# Sheet3.net
KiCad netlist of a schematic drawn in Altium Designer
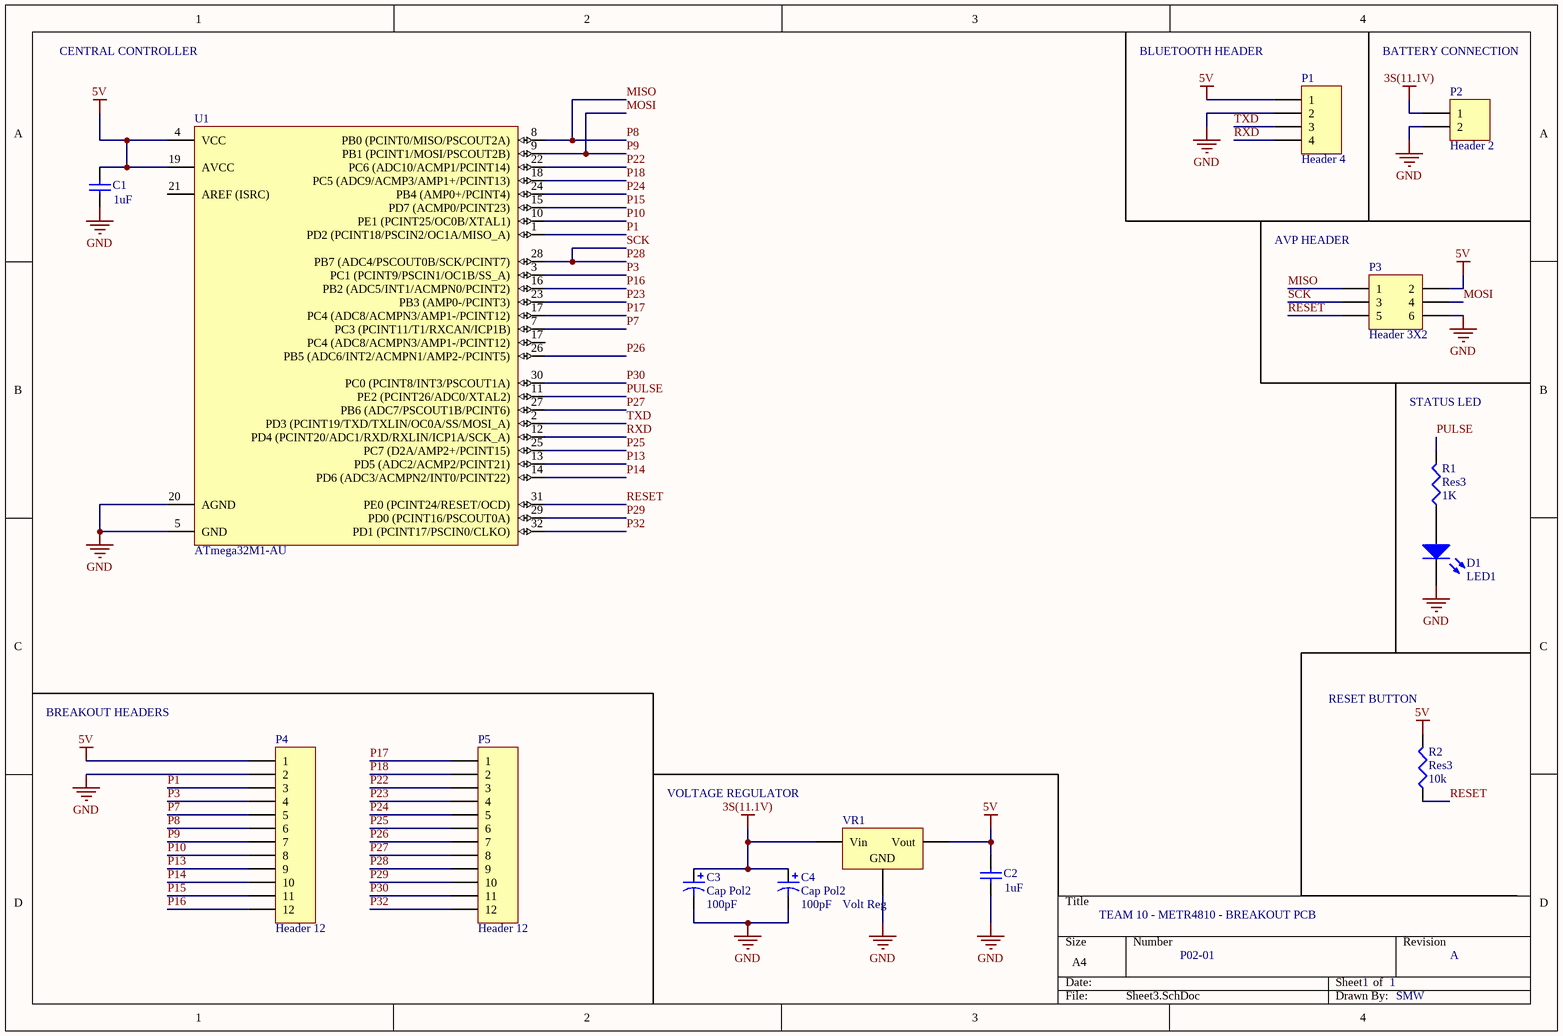
[diagram p0: Sheet3.SchDoc]

(export (version "E")
  (design (tool "Eeschema 10.0.6"))
  (components
    (comp (ref "C1")
      (value "1uF")
      (footprint "1608[0603]")
      (description "Capacitor")
      (fields (field (name "Comment") "Cap") (field (name "PUBLISHER") "Altium Limited"))
      (libsource (lib "Miscellaneous Devices") (part "Cap"))
    )
    (comp (ref "C2")
      (value "1uF")
      (footprint "1608[0603]")
      (description "Capacitor")
      (fields (field (name "Comment") "Cap") (field (name "PUBLISHER") "Altium Limited"))
      (libsource (lib "Miscellaneous Devices") (part "Cap"))
    )
    (comp (ref "C3")
      (value "Cap Pol2")
      (footprint "CAPAE9983X105M")
      (description "Polarized Capacitor (Axial)")
      (fields (field (name "ALTIUM_VALUE") "100pF") (field (name "PUBLISHER") "Altium Limited"))
      (libsource (lib "Miscellaneous Devices") (part "Cap Pol2"))
    )
    (comp (ref "C4")
      (value "Cap Pol2")
      (footprint "CAPAE9983X105M")
      (description "Polarized Capacitor (Axial)")
      (fields (field (name "ALTIUM_VALUE") "100pF") (field (name "PUBLISHER") "Altium Limited"))
      (libsource (lib "Miscellaneous Devices") (part "Cap Pol2"))
    )
    (comp (ref "D1")
      (value "LED1")
      (footprint "L0603")
      (description "Typical RED GaAs LED")
      (fields (field (name "PUBLISHER") "Altium Limited"))
      (libsource (lib "Miscellaneous Devices") (part "LED1"))
    )
    (comp (ref "P1")
      (value "Header 4")
      (footprint "HDR1X4")
      (description "Header, 4-Pin")
      (fields (field (name "PUBLISHER") "Altium Limited"))
      (libsource (lib "Miscellaneous Connectors") (part "Header 4"))
    )
    (comp (ref "P2")
      (value "Header 2")
      (footprint "HDR1X2")
      (description "Header, 2-Pin")
      (fields (field (name "PUBLISHER") "Altium Limited"))
      (libsource (lib "Miscellaneous Connectors") (part "Header 2"))
    )
    (comp (ref "P3")
      (value "Header 3X2")
      (footprint "HDR2X3")
      (description "Header, 3-Pin, Dual row")
      (fields (field (name "PUBLISHER") "Altium Limited"))
      (libsource (lib "Miscellaneous Connectors") (part "Header 3X2"))
    )
    (comp (ref "P4")
      (value "Header 12")
      (footprint "HDR1X12")
      (description "Header, 12-Pin")
      (fields (field (name "PUBLISHER") "Altium Limited"))
      (libsource (lib "Miscellaneous Connectors") (part "Header 12"))
    )
    (comp (ref "P5")
      (value "Header 12")
      (footprint "HDR1X12")
      (description "Header, 12-Pin")
      (fields (field (name "PUBLISHER") "Altium Limited"))
      (libsource (lib "Miscellaneous Connectors") (part "Header 12"))
    )
    (comp (ref "R1")
      (value "Res3")
      (footprint "J1-0603")
      (description "Resistor")
      (fields (field (name "ALTIUM_VALUE") "1K") (field (name "PUBLISHER") "Altium Limited"))
      (libsource (lib "Miscellaneous Devices") (part "Res3"))
    )
    (comp (ref "R2")
      (value "Res3")
      (footprint "J1-0603")
      (description "Resistor")
      (fields (field (name "ALTIUM_VALUE") "10k") (field (name "PUBLISHER") "Altium Limited"))
      (libsource (lib "Miscellaneous Devices") (part "Res3"))
    )
    (comp (ref "U1")
      (value "ATmega32M1-AU")
      (footprint "32A_L")
      (libsource (lib "Atmel Microcontroller AVR Automotive") (part "ATmega32M1-AU"))
    )
    (comp (ref "VR1")
      (value "Volt Reg")
      (footprint "D2PAK_N")
      (description "Voltage Regulator")
      (fields (field (name "PUBLISHER") "Altium Limited"))
      (libsource (lib "Miscellaneous Devices") (part "Volt Reg"))
    )
  )
  (nets
    (net (code "1") (name "/MISO") (class "Default")
      (node (ref "P3") (pin "1") (pinfunction "1_1") (pintype "passive"))
      (node (ref "P4") (pin "6") (pinfunction "6_6") (pintype "passive"))
      (node (ref "U1") (pin "8") (pinfunction "PB0_(PCINT0/MISO/PSCOUT2A)_8") (pintype "bidirectional"))
    )
    (net (code "2") (name "/MOSI") (class "Default")
      (node (ref "P3") (pin "4") (pinfunction "4_4") (pintype "passive"))
      (node (ref "P4") (pin "7") (pinfunction "7_7") (pintype "passive"))
      (node (ref "U1") (pin "9") (pinfunction "PB1_(PCINT1/MOSI/PSCOUT2B)_9") (pintype "bidirectional"))
    )
    (net (code "3") (name "/P1") (class "Default")
      (node (ref "P4") (pin "3") (pinfunction "3_3") (pintype "passive"))
      (node (ref "U1") (pin "1") (pinfunction "PD2_(PCINT18/PSCIN2/OC1A/MISO_A)_1") (pintype "bidirectional"))
    )
    (net (code "4") (name "/P3") (class "Default")
      (node (ref "P4") (pin "4") (pinfunction "4_4") (pintype "passive"))
      (node (ref "U1") (pin "3") (pinfunction "PC1_(PCINT9/PSCIN1/OC1B/SS_A)_3") (pintype "bidirectional"))
    )
    (net (code "5") (name "/P7") (class "Default")
      (node (ref "P4") (pin "5") (pinfunction "5_5") (pintype "passive"))
      (node (ref "U1") (pin "7") (pinfunction "PC3_(PCINT11/T1/RXCAN/ICP1B)_7") (pintype "bidirectional"))
    )
    (net (code "6") (name "/P10") (class "Default")
      (node (ref "P4") (pin "8") (pinfunction "8_8") (pintype "passive"))
      (node (ref "U1") (pin "10") (pinfunction "PE1_(PCINT25/OC0B/XTAL1)_10") (pintype "bidirectional"))
    )
    (net (code "7") (name "/P13") (class "Default")
      (node (ref "P4") (pin "9") (pinfunction "9_9") (pintype "passive"))
      (node (ref "U1") (pin "13") (pinfunction "PD5_(ADC2/ACMP2/PCINT21)_13") (pintype "bidirectional"))
    )
    (net (code "8") (name "/P14") (class "Default")
      (node (ref "P4") (pin "10") (pinfunction "10_10") (pintype "passive"))
      (node (ref "U1") (pin "14") (pinfunction "PD6_(ADC3/ACMPN2/INT0/PCINT22)_14") (pintype "bidirectional"))
    )
    (net (code "9") (name "/P15") (class "Default")
      (node (ref "P4") (pin "11") (pinfunction "11_11") (pintype "passive"))
      (node (ref "U1") (pin "15") (pinfunction "PD7_(ACMP0/PCINT23)_15") (pintype "bidirectional"))
    )
    (net (code "10") (name "/P16") (class "Default")
      (node (ref "P4") (pin "12") (pinfunction "12_12") (pintype "passive"))
      (node (ref "U1") (pin "16") (pinfunction "PB2_(ADC5/INT1/ACMPN0/PCINT2)_16") (pintype "bidirectional"))
    )
    (net (code "11") (name "/P17") (class "Default")
      (node (ref "P5") (pin "1") (pinfunction "1_1") (pintype "passive"))
      (node (ref "U1") (pin "17") (pinfunction "PC4_(ADC8/ACMPN3/AMP1-/PCINT12)_17") (pintype "bidirectional"))
    )
    (net (code "12") (name "/P18") (class "Default")
      (node (ref "P5") (pin "2") (pinfunction "2_2") (pintype "passive"))
      (node (ref "U1") (pin "18") (pinfunction "PC5_(ADC9/ACMP3/AMP1+/PCINT13)_18") (pintype "bidirectional"))
    )
    (net (code "13") (name "/P22") (class "Default")
      (node (ref "P5") (pin "3") (pinfunction "3_3") (pintype "passive"))
      (node (ref "U1") (pin "22") (pinfunction "PC6_(ADC10/ACMP1/PCINT14)_22") (pintype "bidirectional"))
    )
    (net (code "14") (name "/P23") (class "Default")
      (node (ref "P5") (pin "4") (pinfunction "4_4") (pintype "passive"))
      (node (ref "U1") (pin "23") (pinfunction "PB3_(AMP0-/PCINT3)_23") (pintype "bidirectional"))
    )
    (net (code "15") (name "/P24") (class "Default")
      (node (ref "P5") (pin "5") (pinfunction "5_5") (pintype "passive"))
      (node (ref "U1") (pin "24") (pinfunction "PB4_(AMP0+/PCINT4)_24") (pintype "bidirectional"))
    )
    (net (code "16") (name "/P25") (class "Default")
      (node (ref "P5") (pin "6") (pinfunction "6_6") (pintype "passive"))
      (node (ref "U1") (pin "25") (pinfunction "PC7_(D2A/AMP2+/PCINT15)_25") (pintype "bidirectional"))
    )
    (net (code "17") (name "/P26") (class "Default")
      (node (ref "P5") (pin "7") (pinfunction "7_7") (pintype "passive"))
      (node (ref "U1") (pin "26") (pinfunction "PB5_(ADC6/INT2/ACMPN1/AMP2-/PCINT5)_26") (pintype "bidirectional"))
    )
    (net (code "18") (name "/P27") (class "Default")
      (node (ref "P5") (pin "8") (pinfunction "8_8") (pintype "passive"))
      (node (ref "U1") (pin "27") (pinfunction "PB6_(ADC7/PSCOUT1B/PCINT6)_27") (pintype "bidirectional"))
    )
    (net (code "19") (name "/P28") (class "Default")
      (node (ref "P3") (pin "3") (pinfunction "3_3") (pintype "passive"))
      (node (ref "P5") (pin "9") (pinfunction "9_9") (pintype "passive"))
      (node (ref "U1") (pin "28") (pinfunction "PB7_(ADC4/PSCOUT0B/SCK/PCINT7)_28") (pintype "bidirectional"))
    )
    (net (code "20") (name "/P29") (class "Default")
      (node (ref "P5") (pin "10") (pinfunction "10_10") (pintype "passive"))
      (node (ref "U1") (pin "29") (pinfunction "PD0_(PCINT16/PSCOUT0A)_29") (pintype "bidirectional"))
    )
    (net (code "21") (name "/P30") (class "Default")
      (node (ref "P5") (pin "11") (pinfunction "11_11") (pintype "passive"))
      (node (ref "U1") (pin "30") (pinfunction "PC0_(PCINT8/INT3/PSCOUT1A)_30") (pintype "bidirectional"))
    )
    (net (code "22") (name "/P32") (class "Default")
      (node (ref "P5") (pin "12") (pinfunction "12_12") (pintype "passive"))
      (node (ref "U1") (pin "32") (pinfunction "PD1_(PCINT17/PSCIN0/CLKO)_32") (pintype "bidirectional"))
    )
    (net (code "23") (name "/PULSE") (class "Default")
      (node (ref "R1") (pin "2") (pinfunction "2_2") (pintype "passive"))
      (node (ref "U1") (pin "11") (pinfunction "PE2_(PCINT26/ADC0/XTAL2)_11") (pintype "bidirectional"))
    )
    (net (code "24") (name "/RESET") (class "Default")
      (node (ref "P3") (pin "5") (pinfunction "5_5") (pintype "passive"))
      (node (ref "R2") (pin "1") (pinfunction "1_1") (pintype "passive"))
      (node (ref "U1") (pin "31") (pinfunction "PE0_(PCINT24/RESET/OCD)_31") (pintype "bidirectional"))
    )
    (net (code "25") (name "/RXD") (class "Default")
      (node (ref "P1") (pin "4") (pinfunction "4_4") (pintype "passive"))
      (node (ref "U1") (pin "12") (pinfunction "PD4_(PCINT20/ADC1/RXD/RXLIN/ICP1A/SCK_A)_12") (pintype "bidirectional"))
    )
    (net (code "26") (name "/TXD") (class "Default")
      (node (ref "P1") (pin "3") (pinfunction "3_3") (pintype "passive"))
      (node (ref "U1") (pin "2") (pinfunction "PD3_(PCINT19/TXD/TXLIN/OC0A/SS/MOSI_A)_2") (pintype "bidirectional"))
    )
    (net (code "27") (name "3S(11.1V)") (class "Default")
      (node (ref "C3") (pin "1") (pinfunction "1_1") (pintype "passive"))
      (node (ref "C4") (pin "1") (pinfunction "1_1") (pintype "passive"))
      (node (ref "P2") (pin "1") (pinfunction "1_1") (pintype "passive"))
      (node (ref "VR1") (pin "1") (pinfunction "Vin_1") (pintype "passive"))
    )
    (net (code "28") (name "5V") (class "Default")
      (node (ref "C1") (pin "2") (pinfunction "2_2") (pintype "passive"))
      (node (ref "C2") (pin "2") (pinfunction "2_2") (pintype "passive"))
      (node (ref "P1") (pin "1") (pinfunction "1_1") (pintype "passive"))
      (node (ref "P3") (pin "2") (pinfunction "2_2") (pintype "passive"))
      (node (ref "P4") (pin "1") (pinfunction "1_1") (pintype "passive"))
      (node (ref "R2") (pin "2") (pinfunction "2_2") (pintype "passive"))
      (node (ref "U1") (pin "19") (pinfunction "AVCC_19") (pintype "power_in"))
      (node (ref "U1") (pin "4") (pinfunction "VCC_4") (pintype "power_in"))
      (node (ref "VR1") (pin "3") (pinfunction "Vout_3") (pintype "passive"))
    )
    (net (code "29") (name "GND") (class "Default")
      (node (ref "C1") (pin "1") (pinfunction "1_1") (pintype "passive"))
      (node (ref "C2") (pin "1") (pinfunction "1_1") (pintype "passive"))
      (node (ref "C3") (pin "2") (pinfunction "2_2") (pintype "passive"))
      (node (ref "C4") (pin "2") (pinfunction "2_2") (pintype "passive"))
      (node (ref "D1") (pin "2") (pinfunction "K_2") (pintype "passive"))
      (node (ref "P1") (pin "2") (pinfunction "2_2") (pintype "passive"))
      (node (ref "P2") (pin "2") (pinfunction "2_2") (pintype "passive"))
      (node (ref "P3") (pin "6") (pinfunction "6_6") (pintype "passive"))
      (node (ref "P4") (pin "2") (pinfunction "2_2") (pintype "passive"))
      (node (ref "U1") (pin "20") (pinfunction "AGND_20") (pintype "power_in"))
      (node (ref "U1") (pin "5") (pinfunction "GND_5") (pintype "power_in"))
      (node (ref "VR1") (pin "2") (pinfunction "GND_2") (pintype "passive"))
    )
    (net (code "30") (name "Net-(D1-A)") (class "Default")
      (node (ref "D1") (pin "1") (pinfunction "A_1") (pintype "passive"))
      (node (ref "R1") (pin "1") (pinfunction "1_1") (pintype "passive"))
    )
    (net (code "31") (name "unconnected-(U1-AREF_(ISRC)-Pad21)") (class "Default")
      (node (ref "U1") (pin "21") (pinfunction "AREF_(ISRC)_21") (pintype "power_in"))
    )
    (net (code "32") (name "unconnected-(U1-PC4_(ADC8{slash}ACMPN3{slash}AMP1-{slash}PCINT12)-Pad17)") (class "Default")
      (node (ref "U1") (pin "17") (pinfunction "PC4_(ADC8/ACMPN3/AMP1-/PCINT12)_17") (pintype "bidirectional"))
    )
  )
)
